# jtag.net
KiCad netlist of a schematic drawn in Altium Designer
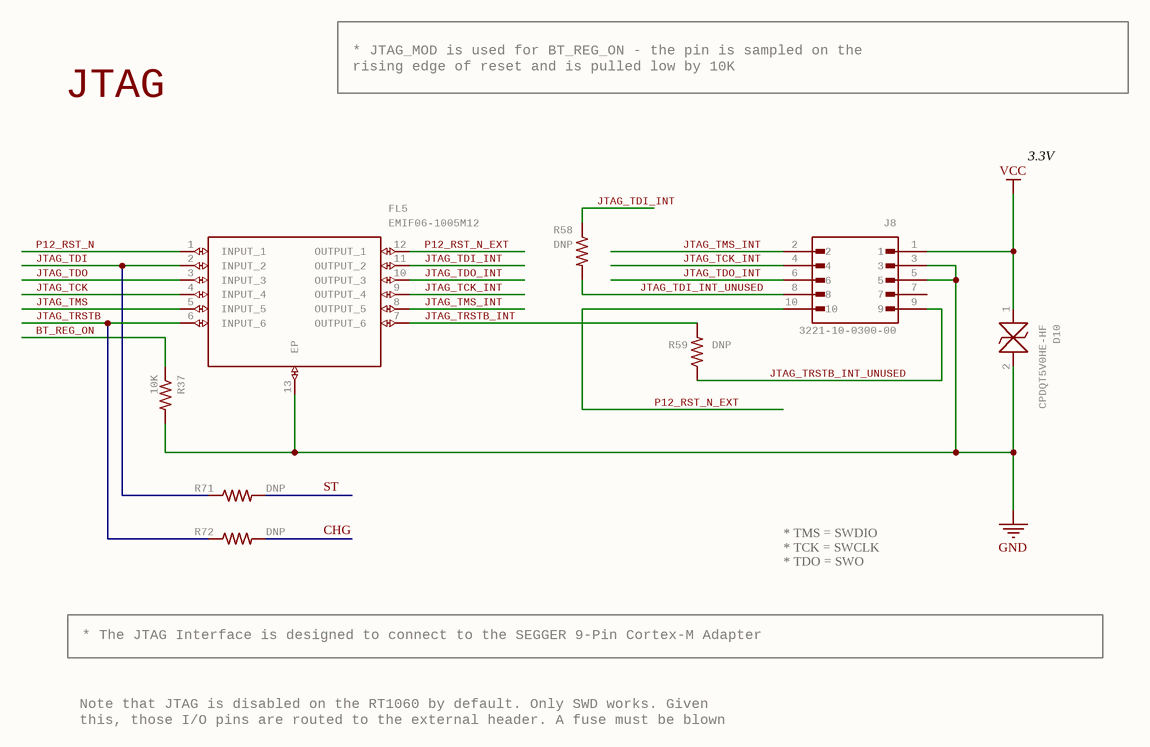
[diagram p0: jtag.SchDoc]

(export (version "E")
  (design (tool "Eeschema 10.0.6"))
  (components
    (comp (ref "D10")
      (value "CPDQT5V0HE-HF")
      (footprint "CPDQT5V0HEHF")
      (description "ESD Suppressors / TVS Diodes DIODE ESD 5VWM 65W 0402/SOD-923F   Source:  Datasheet")
      (fields (field (name "MOUSER_PART_NUMBER") "MOUSER_PART_NUMBER"))
      (libsource (lib "rt10") (part "CPDQT5V0HE-HF"))
    )
    (comp (ref "FL5")
      (value "EMIF06-1005M12")
      (footprint "SON40P150X250X65-13N")
      (description "EMI Filter Circuits 6lin lw cpcitnc EMI 45pF -35db @ 900MHz   Source:  Datasheet")
      (fields (field (name "MOUSER_PART_NUMBER") "511-EMIF06-1005M12"))
      (libsource (lib "rt10") (part "EMIF06-1005M12"))
    )
    (comp (ref "J8")
      (value "3221-10-0300-00")
      (footprint "CNC_3221-10-0300-00")
      (description "Check availability")
      (fields (field (name "MF") "CNC Tech"))
      (libsource (lib "rt10") (part "3221-10-0300-00"))
    )
    (comp (ref "R37")
      (value "10K")
      (footprint "0402-RES")
      (description "ResistorBasic schematic elements and footprints for 0603, 1206, and PTH resistors.")
      (fields (field (name "MPN") "AC0402FR-1310KL") (field (name "LIBRARYNAME") "sfe"))
      (libsource (lib "rt10") (part "RESISTOR0402-RES"))
    )
    (comp (ref "R58")
      (value "DNP")
      (footprint "0402-RES")
      (description "ResistorBasic schematic elements and footprints for 0603, 1206, and PTH resistors.")
      (fields (field (name "LIBRARYNAME") "sfe"))
      (libsource (lib "rt10") (part "RESISTOR0402-RES"))
    )
    (comp (ref "R59")
      (value "DNP")
      (footprint "0402-RES")
      (description "ResistorBasic schematic elements and footprints for 0603, 1206, and PTH resistors.")
      (fields (field (name "LIBRARYNAME") "sfe"))
      (libsource (lib "rt10") (part "RESISTOR0402-RES"))
    )
    (comp (ref "R71")
      (value "DNP")
      (footprint "0402-RES")
      (description "ResistorBasic schematic elements and footprints for 0603, 1206, and PTH resistors.")
      (fields (field (name "LIBRARYNAME") "sfe"))
      (libsource (lib "rt10") (part "RESISTOR0402-RES"))
    )
    (comp (ref "R72")
      (value "DNP")
      (footprint "0402-RES")
      (description "ResistorBasic schematic elements and footprints for 0603, 1206, and PTH resistors.")
      (fields (field (name "LIBRARYNAME") "sfe"))
      (libsource (lib "rt10") (part "RESISTOR0402-RES"))
    )
  )
  (nets
    (net (code "1") (name "/BT_REG_ON") (class "Default")
      (node (ref "R37") (pin "1") (pinfunction "1_1") (pintype "passive"))
    )
    (net (code "2") (name "/CHG") (class "Default")
      (node (ref "R72") (pin "2") (pinfunction "2_2") (pintype "passive"))
    )
    (net (code "3") (name "/JTAG_TCK") (class "Default")
      (node (ref "FL5") (pin "4") (pinfunction "INPUT_4_4") (pintype "bidirectional"))
    )
    (net (code "4") (name "/JTAG_TCK_INT") (class "Default")
      (node (ref "FL5") (pin "9") (pinfunction "OUTPUT_4_9") (pintype "bidirectional"))
      (node (ref "J8") (pin "4") (pinfunction "4_4") (pintype "passive"))
    )
    (net (code "5") (name "/JTAG_TDI") (class "Default")
      (node (ref "FL5") (pin "2") (pinfunction "INPUT_2_2") (pintype "bidirectional"))
      (node (ref "R71") (pin "1") (pinfunction "1_1") (pintype "passive"))
    )
    (net (code "6") (name "/JTAG_TDI_INT") (class "Default")
      (node (ref "FL5") (pin "11") (pinfunction "OUTPUT_2_11") (pintype "bidirectional"))
      (node (ref "R58") (pin "1") (pinfunction "1_1") (pintype "passive"))
    )
    (net (code "7") (name "/JTAG_TDI_INT_UNUSED") (class "Default")
      (node (ref "J8") (pin "8") (pinfunction "8_8") (pintype "passive"))
      (node (ref "R58") (pin "2") (pinfunction "2_2") (pintype "passive"))
    )
    (net (code "8") (name "/JTAG_TDO") (class "Default")
      (node (ref "FL5") (pin "3") (pinfunction "INPUT_3_3") (pintype "bidirectional"))
    )
    (net (code "9") (name "/JTAG_TDO_INT") (class "Default")
      (node (ref "FL5") (pin "10") (pinfunction "OUTPUT_3_10") (pintype "bidirectional"))
      (node (ref "J8") (pin "6") (pinfunction "6_6") (pintype "passive"))
    )
    (net (code "10") (name "/JTAG_TMS") (class "Default")
      (node (ref "FL5") (pin "5") (pinfunction "INPUT_5_5") (pintype "bidirectional"))
    )
    (net (code "11") (name "/JTAG_TMS_INT") (class "Default")
      (node (ref "FL5") (pin "8") (pinfunction "OUTPUT_5_8") (pintype "bidirectional"))
      (node (ref "J8") (pin "2") (pinfunction "2_2") (pintype "passive"))
    )
    (net (code "12") (name "/JTAG_TRSTB") (class "Default")
      (node (ref "FL5") (pin "6") (pinfunction "INPUT_6_6") (pintype "bidirectional"))
      (node (ref "R72") (pin "1") (pinfunction "1_1") (pintype "passive"))
    )
    (net (code "13") (name "/JTAG_TRSTB_INT") (class "Default")
      (node (ref "FL5") (pin "7") (pinfunction "OUTPUT_6_7") (pintype "bidirectional"))
      (node (ref "R59") (pin "2") (pinfunction "2_2") (pintype "passive"))
    )
    (net (code "14") (name "/JTAG_TRSTB_INT_UNUSED") (class "Default")
      (node (ref "J8") (pin "9") (pinfunction "9_9") (pintype "passive"))
      (node (ref "R59") (pin "1") (pinfunction "1_1") (pintype "passive"))
    )
    (net (code "15") (name "/P12_RST_N") (class "Default")
      (node (ref "FL5") (pin "1") (pinfunction "INPUT_1_1") (pintype "bidirectional"))
    )
    (net (code "16") (name "/P12_RST_N_EXT") (class "Default")
      (node (ref "FL5") (pin "12") (pinfunction "OUTPUT_1_12") (pintype "bidirectional"))
      (node (ref "J8") (pin "10") (pinfunction "10_10") (pintype "passive"))
    )
    (net (code "17") (name "/ST") (class "Default")
      (node (ref "R71") (pin "2") (pinfunction "2_2") (pintype "passive"))
    )
    (net (code "18") (name "GND") (class "Default")
      (node (ref "D10") (pin "2") (pinfunction "2_2") (pintype "bidirectional"))
      (node (ref "FL5") (pin "13") (pinfunction "EP_13") (pintype "bidirectional"))
      (node (ref "J8") (pin "3") (pinfunction "3_3") (pintype "passive"))
      (node (ref "J8") (pin "5") (pinfunction "5_5") (pintype "passive"))
      (node (ref "R37") (pin "2") (pinfunction "2_2") (pintype "passive"))
    )
    (net (code "19") (name "VCC") (class "Default")
      (node (ref "D10") (pin "1") (pinfunction "1_1") (pintype "bidirectional"))
      (node (ref "J8") (pin "1") (pinfunction "1_1") (pintype "passive"))
    )
    (net (code "20") (name "unconnected-(J8-Pad7)") (class "Default")
      (node (ref "J8") (pin "7") (pinfunction "7_7") (pintype "passive"))
    )
  )
)
